# CruiseControlSystemWiringSchematic_11_28.net
KiCad netlist of a schematic drawn in EasyEDA
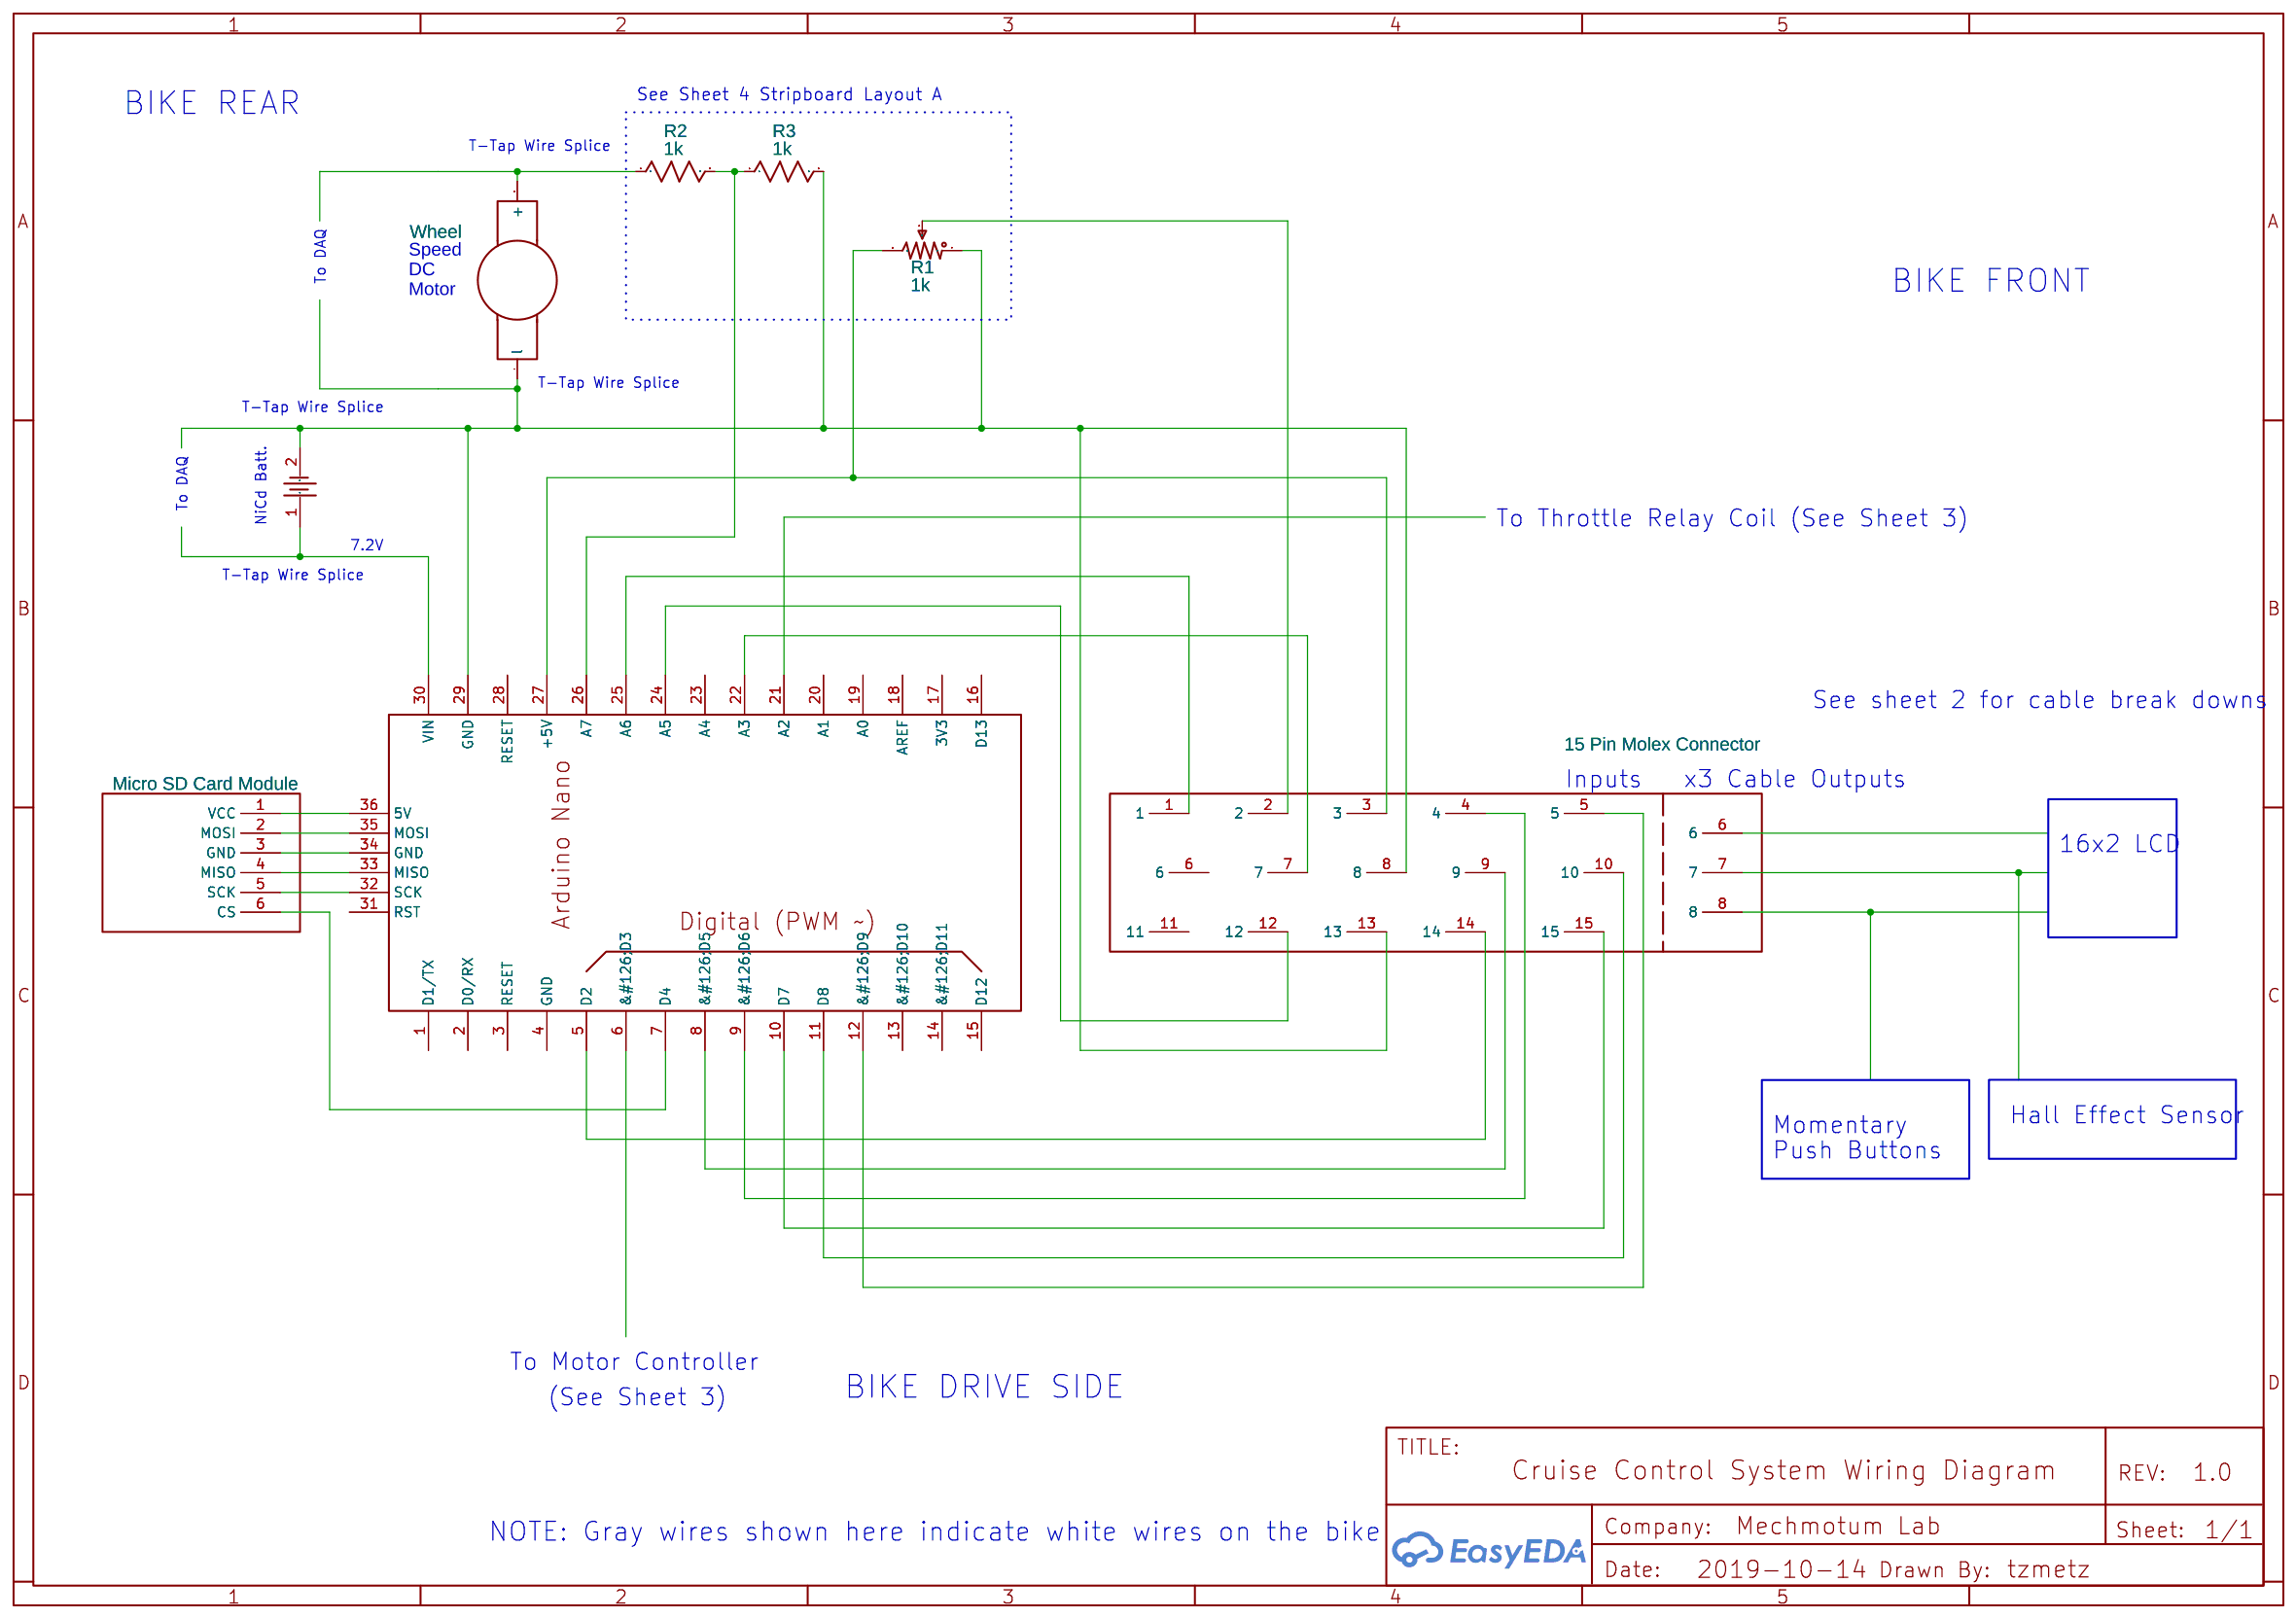
[diagram p0: Sheet_1]
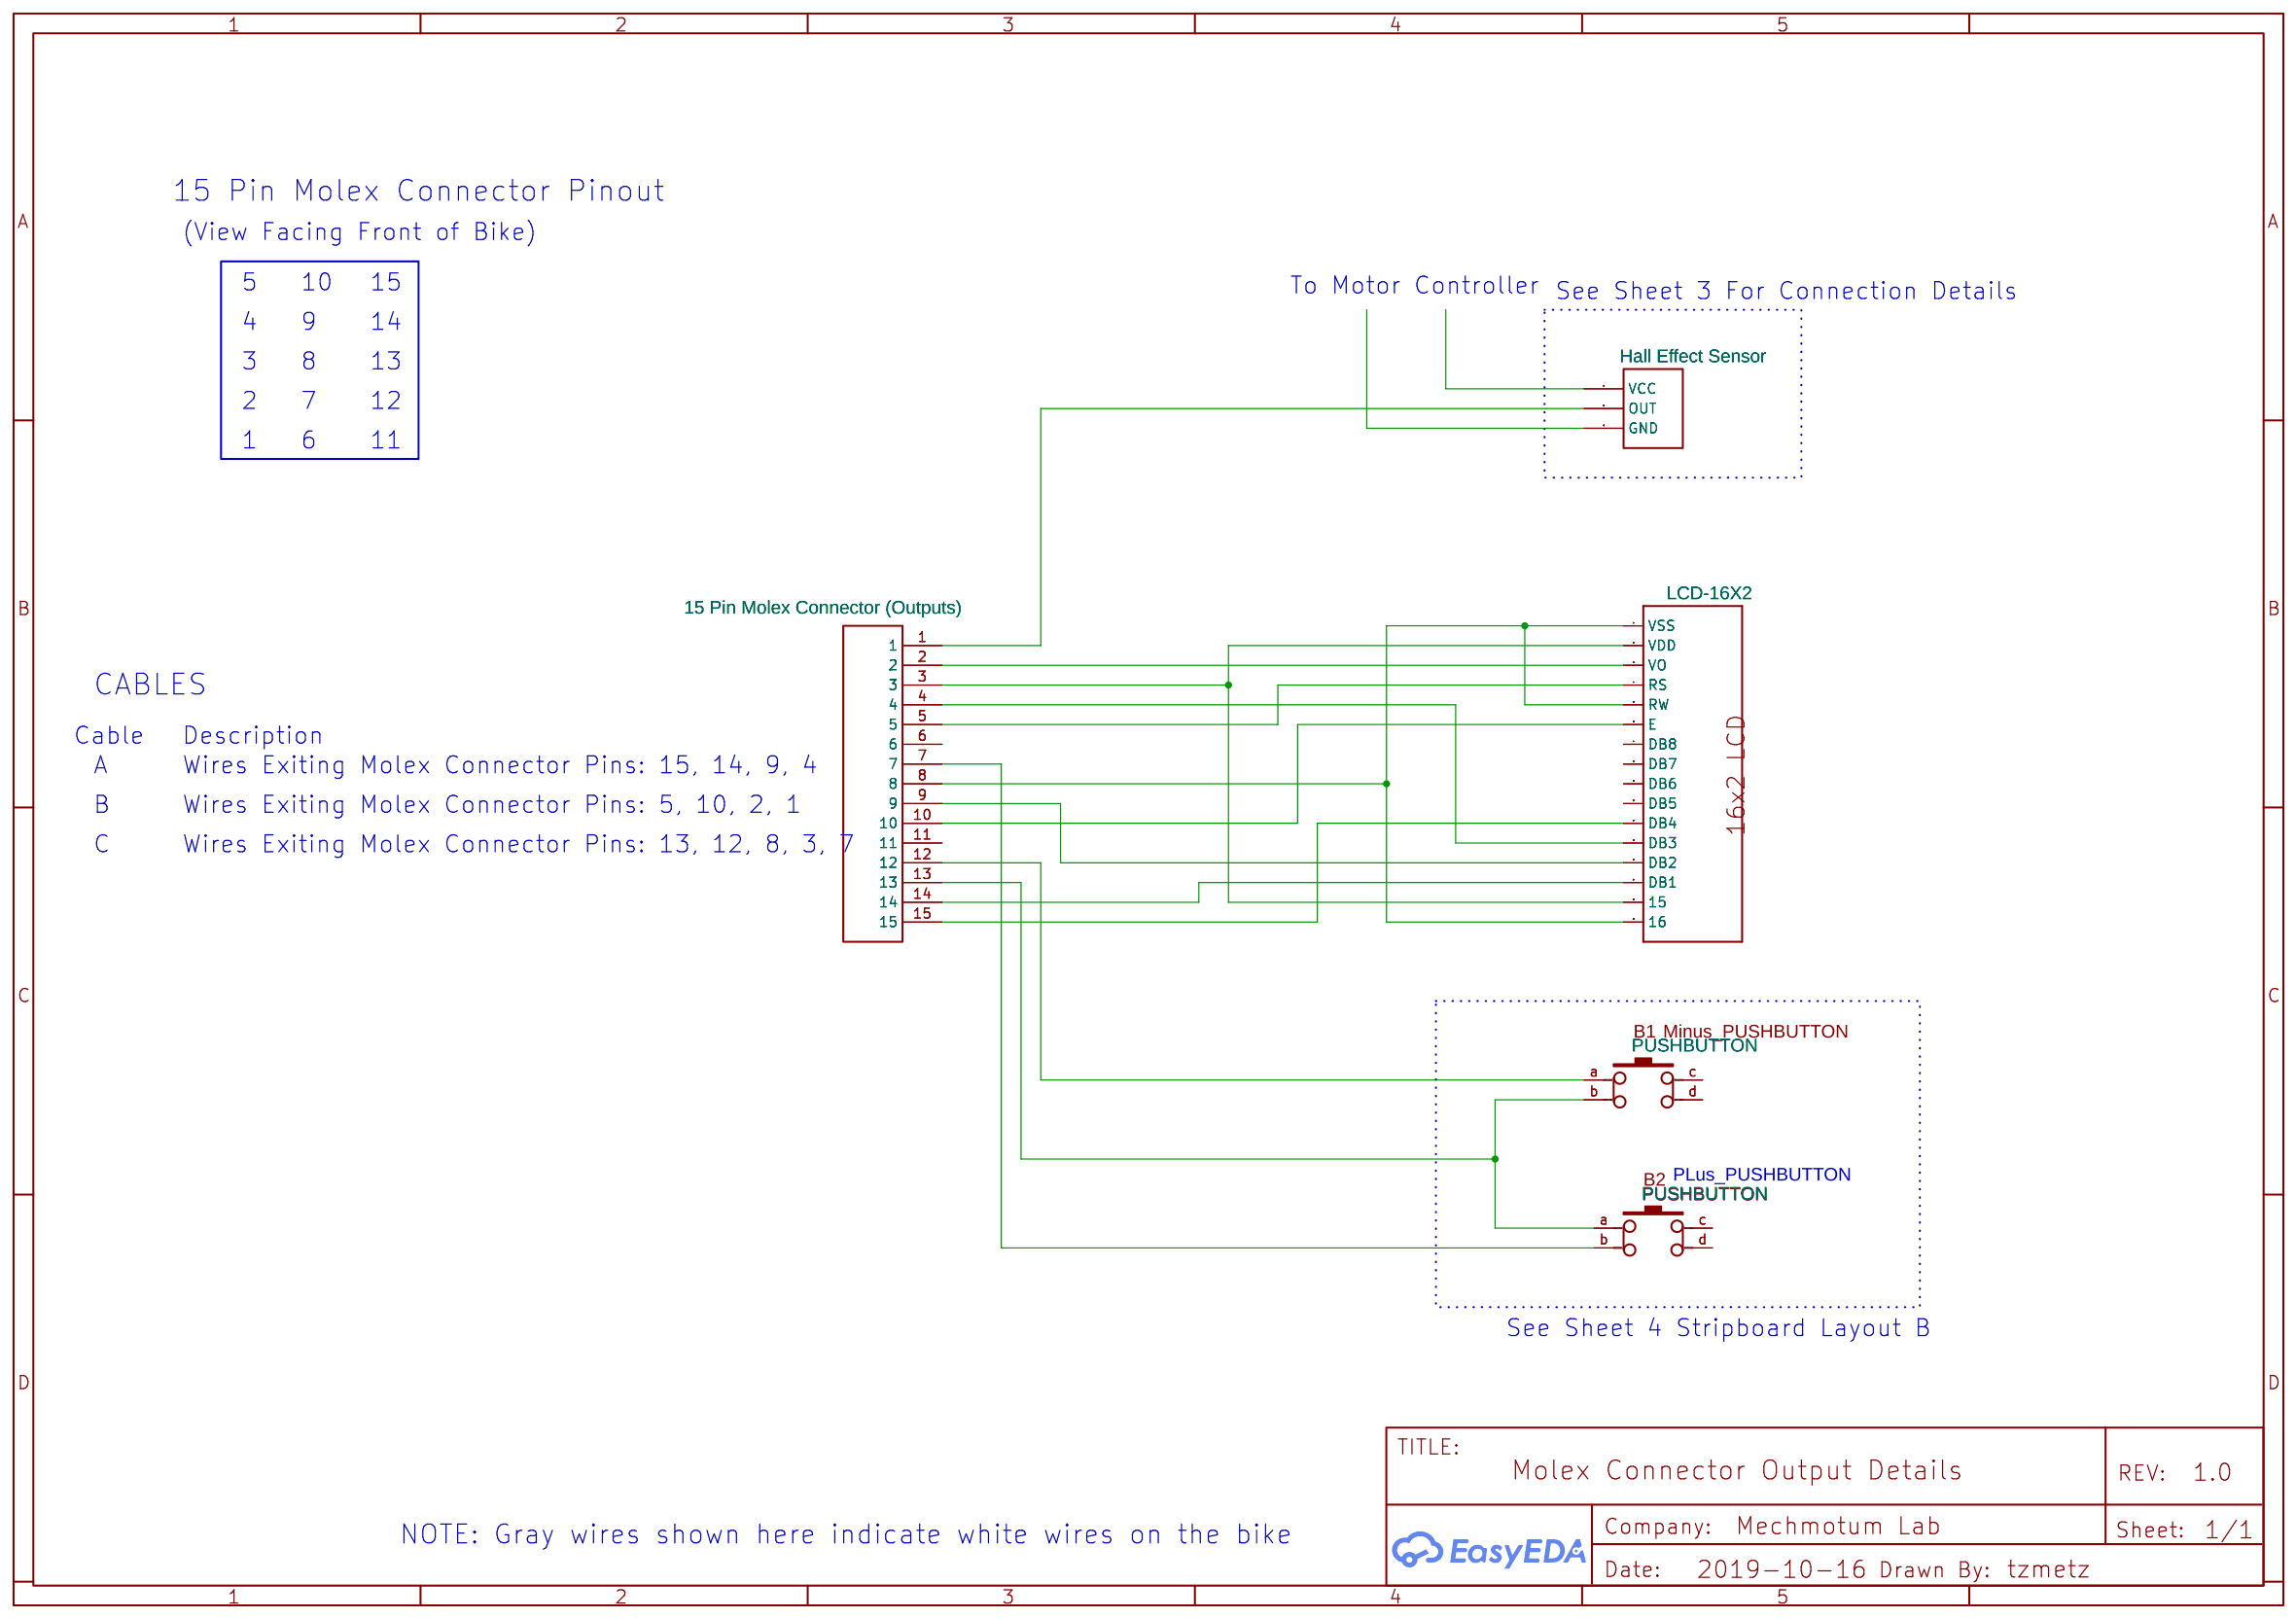
[diagram p1: Sheet_2]
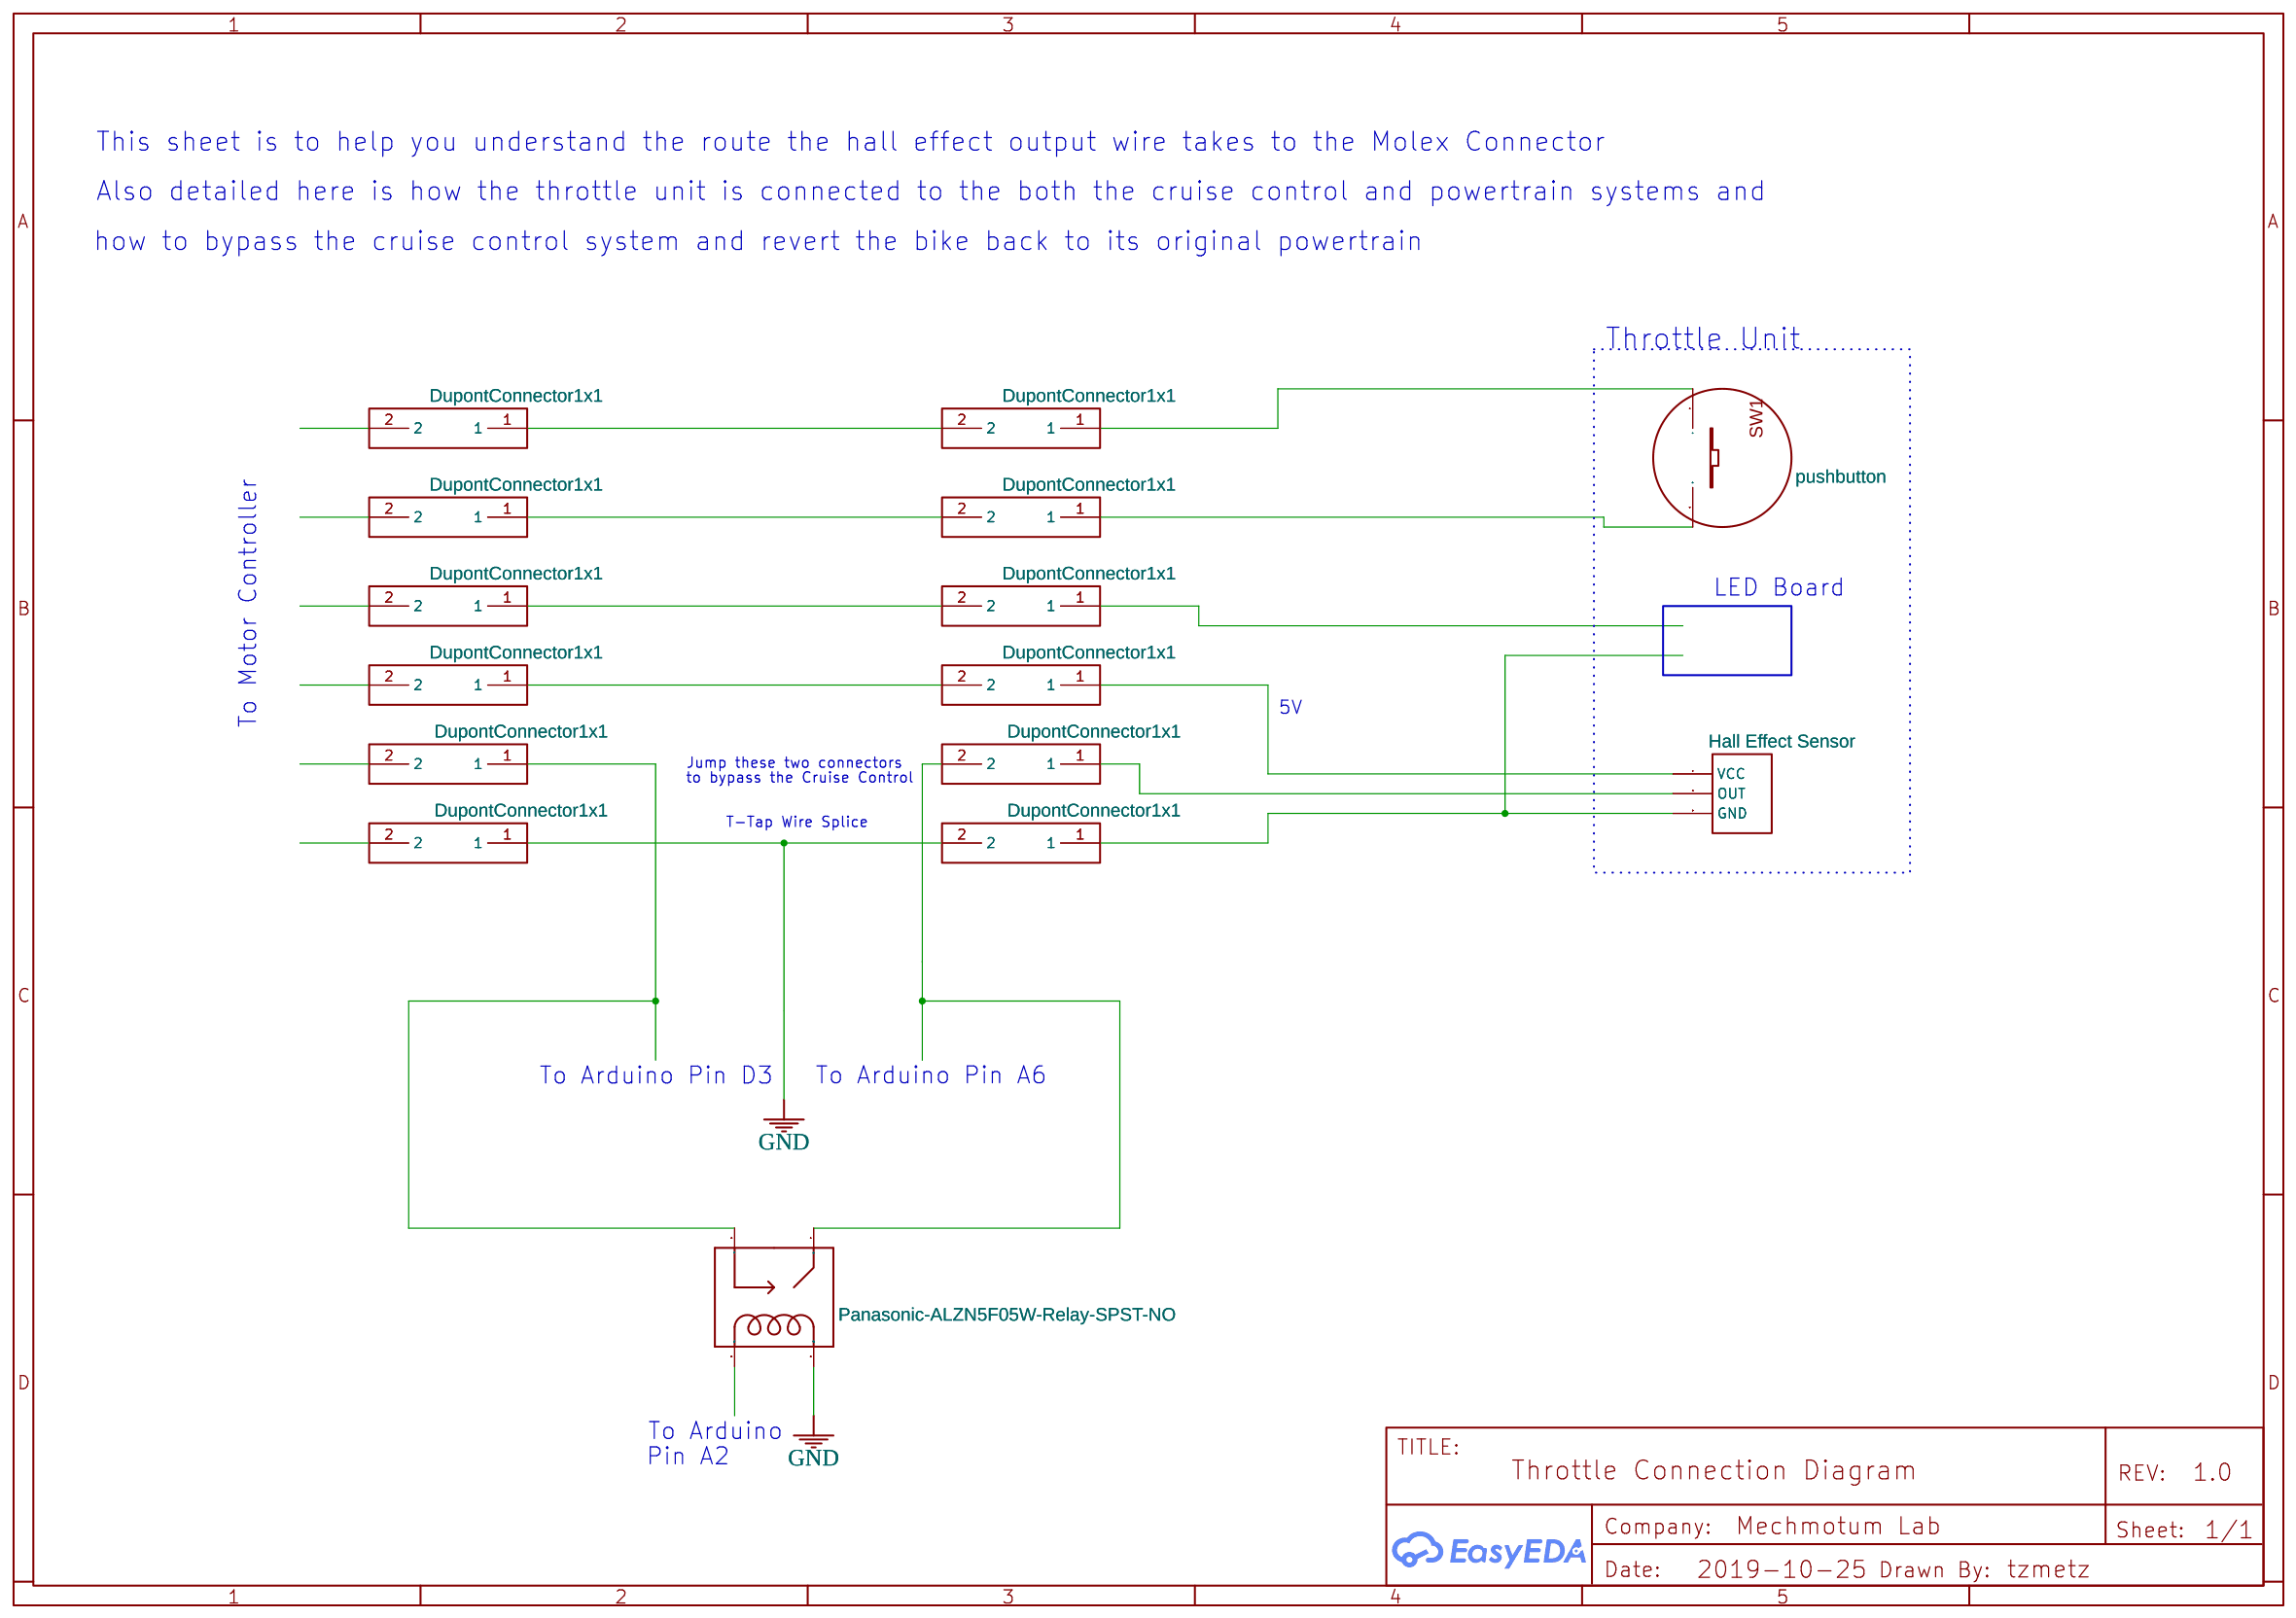
[diagram p2: Sheet_3]
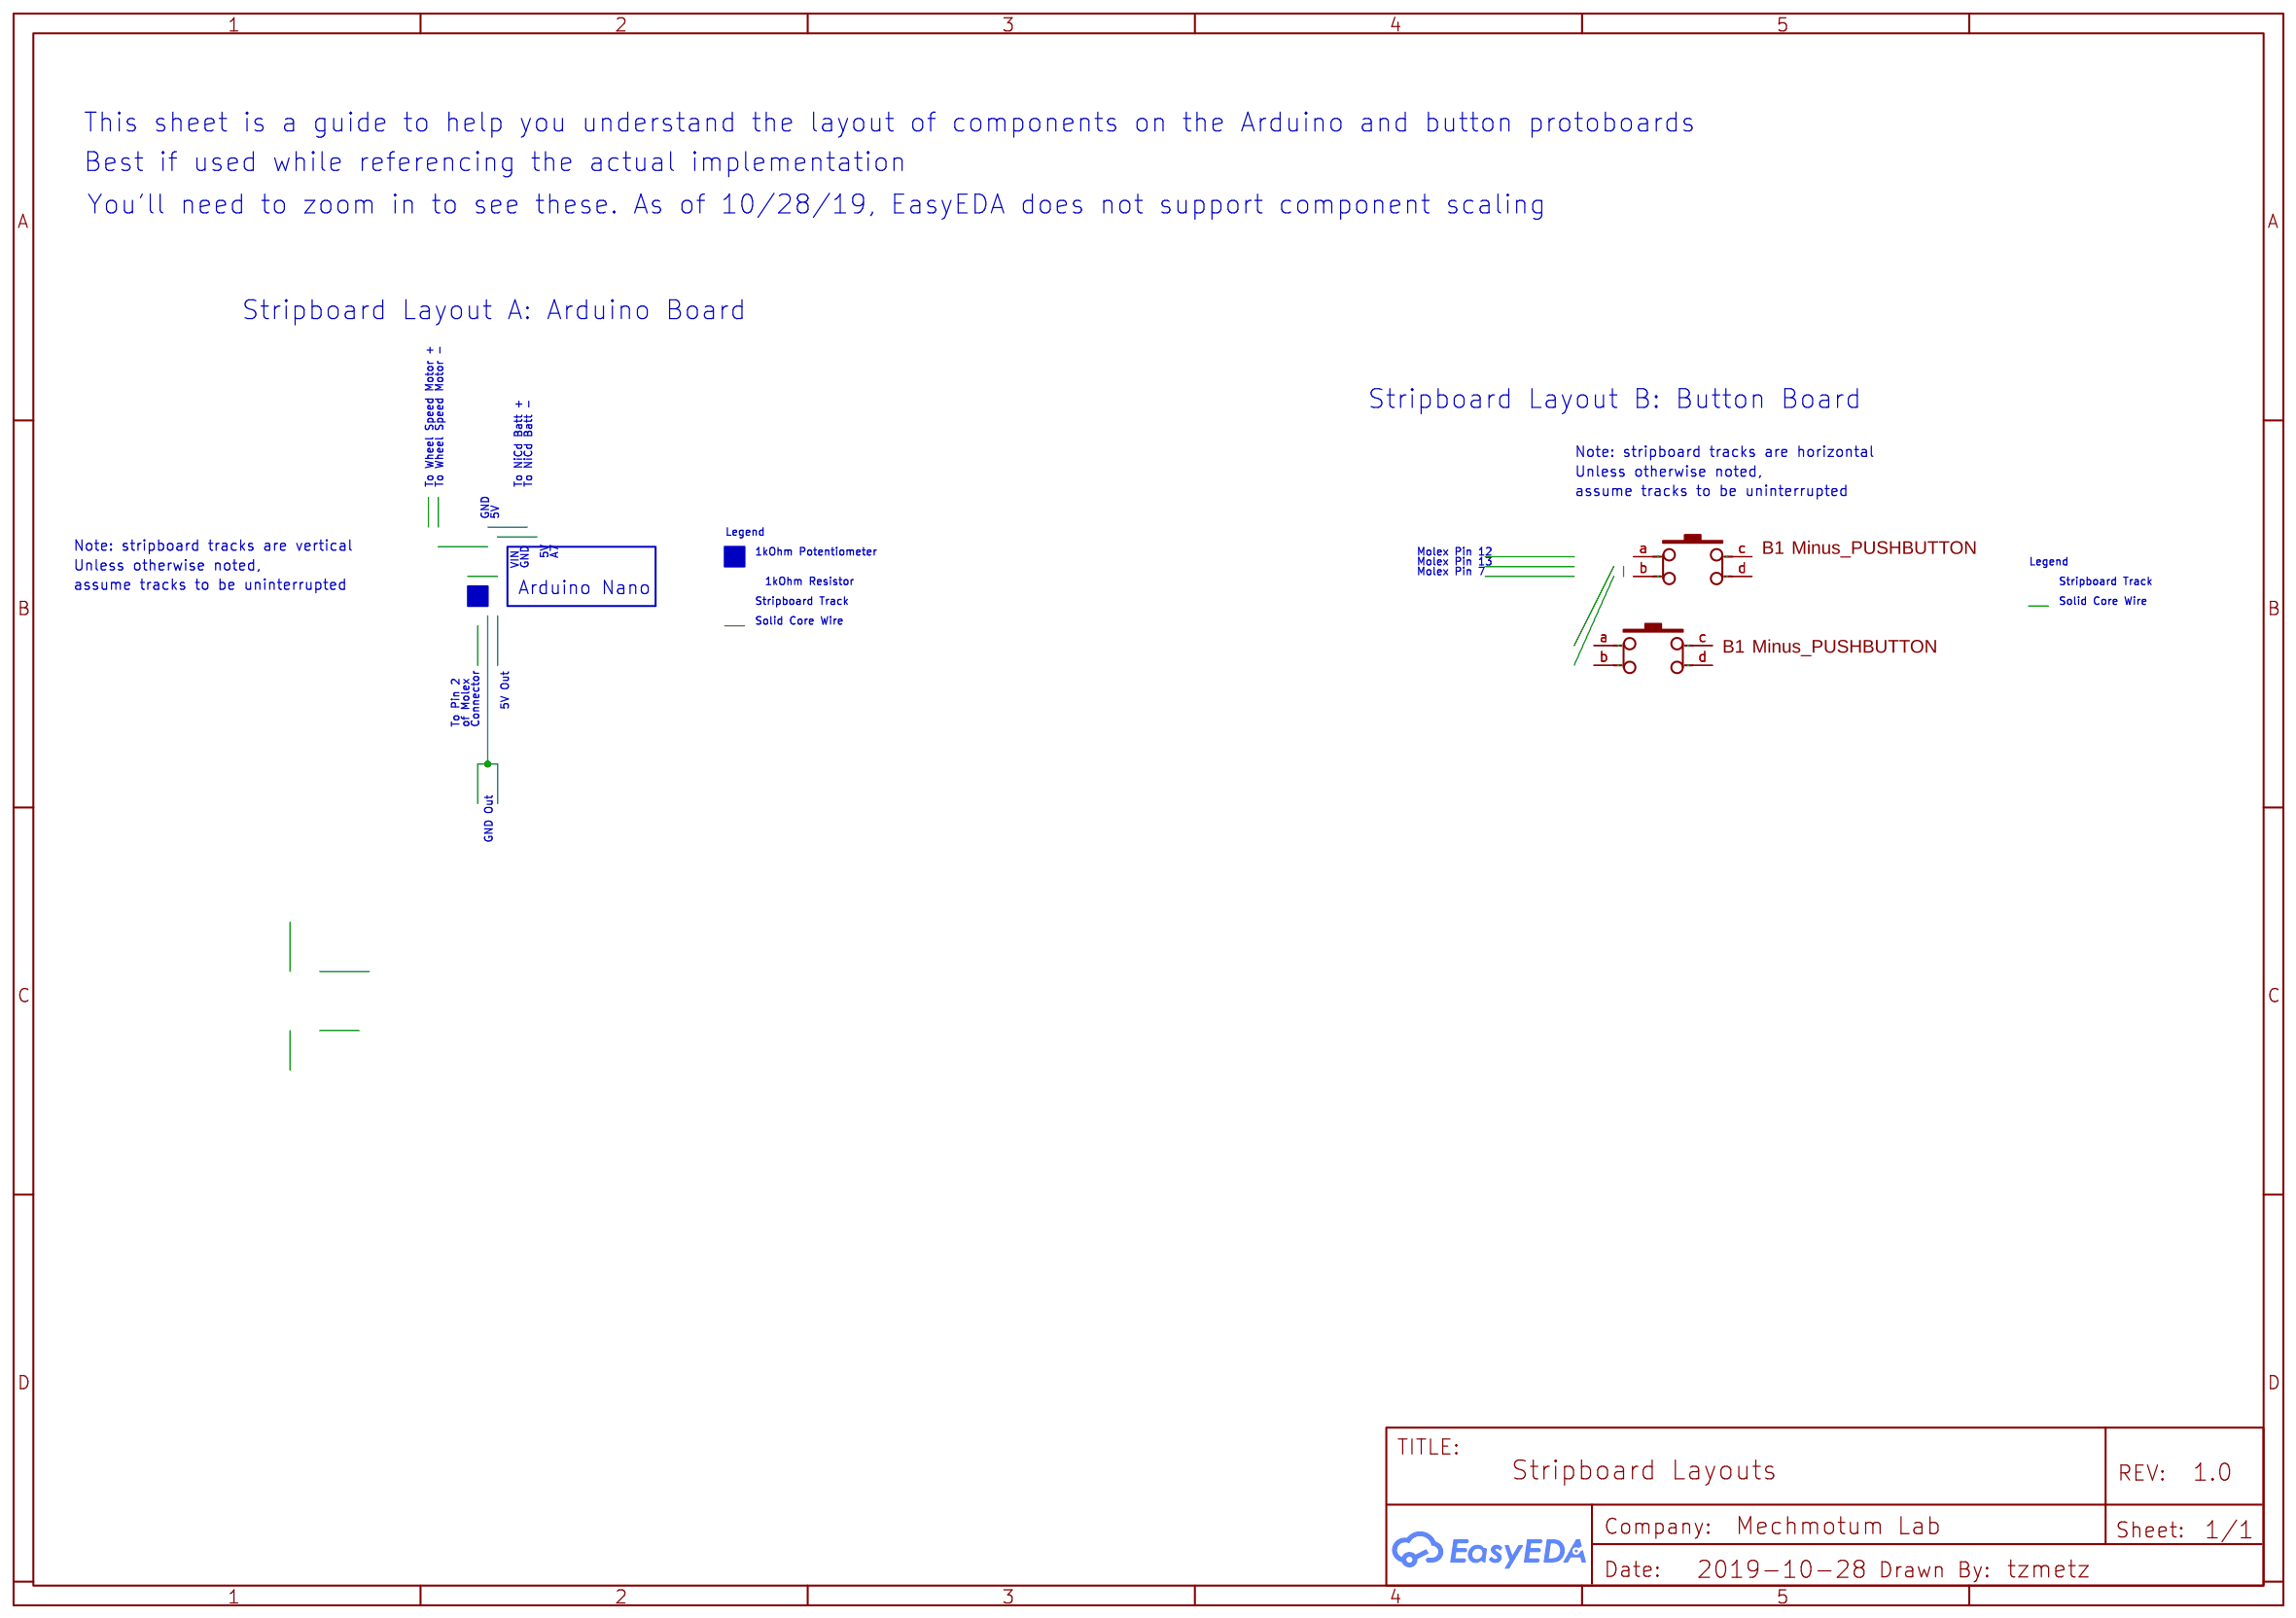
[diagram p3: Sheet_4]
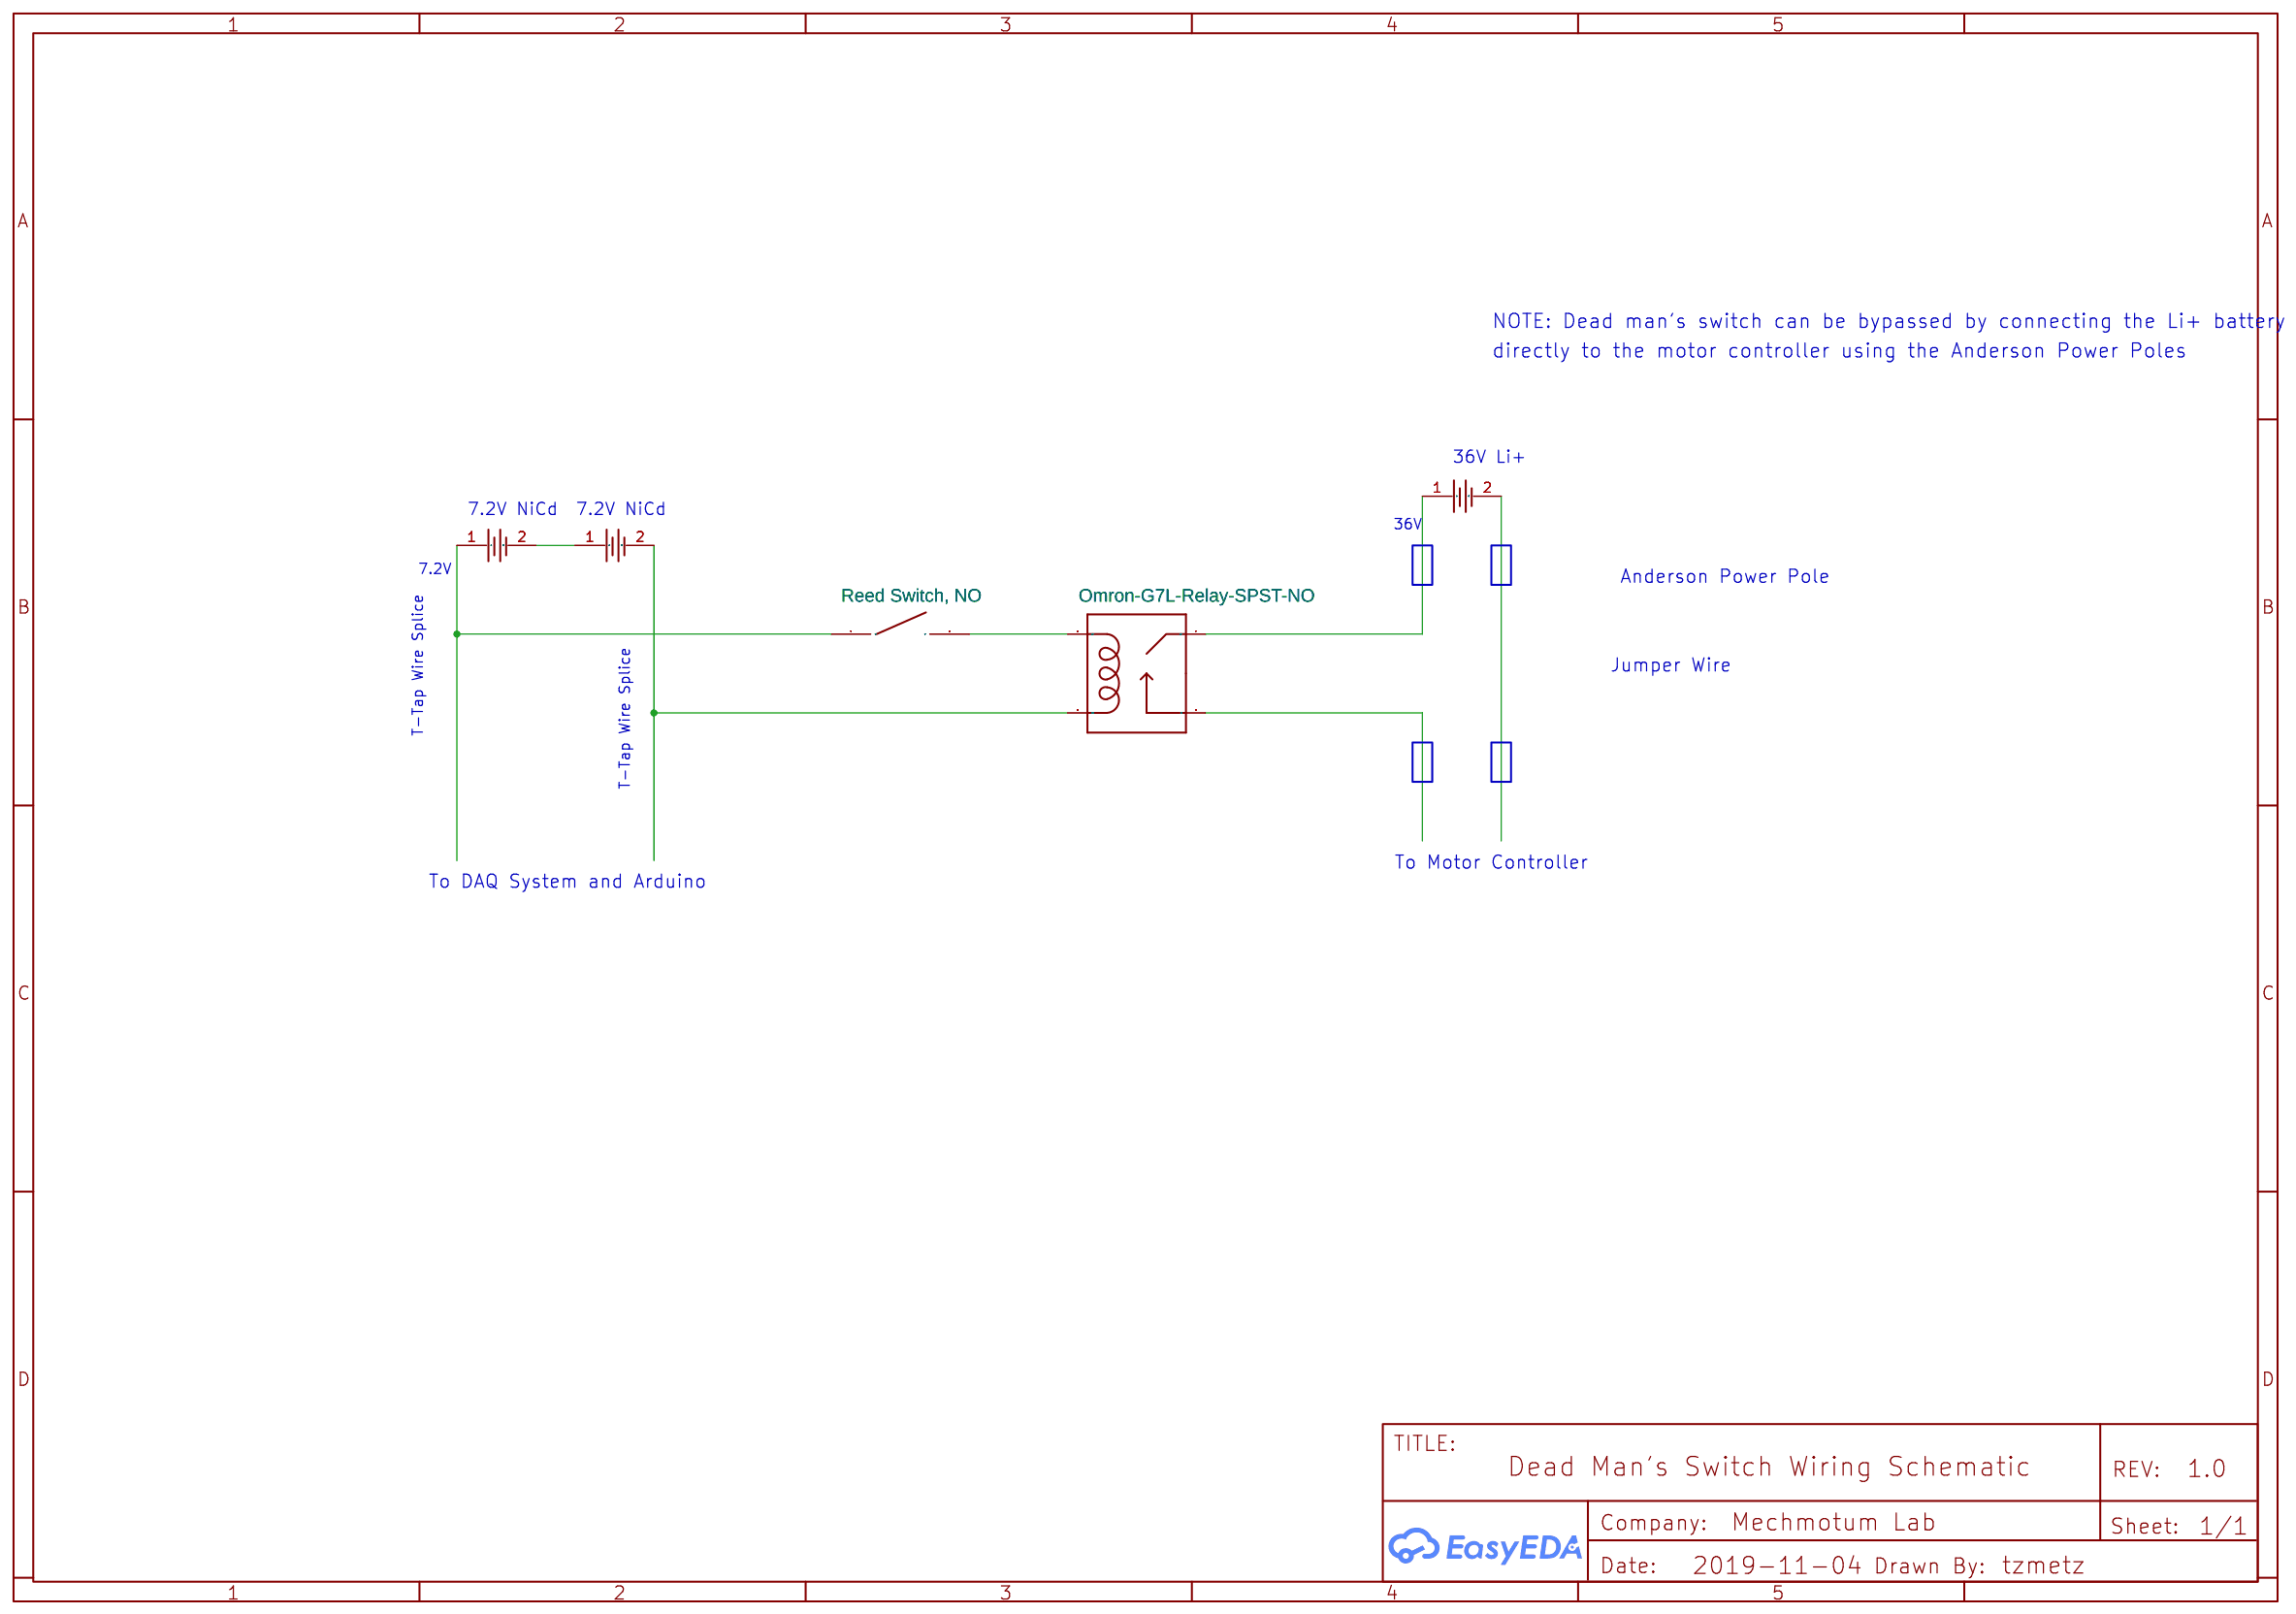
[diagram p4: Sheet_5]

(export (version "E")
  (design (tool "Eeschema 10.0.6"))
  (components
    (comp (ref "B1")
      (value "NiCd Battery 7.2V Line")
      (fields (field (name "BOM_Manufacturer Part") "BS-2-1") (field (name "BOM_Supplier Part") "C70376"))
      (libsource (lib "") (part "Unknown_145_240"))
    )
    (comp (ref "R1")
      (value "1k")
      (fields
        (field (name "BOM_Manufacturer Part") "3386P-1-101LF")
        (field (name "BOM_Supplier Part") "C125022")
      )
      (libsource (lib "") (part "3386P-1-101LF_US"))
    )
    (comp (ref "R2") (value "1k") (libsource (lib "") (part "Res_AXIAL-0.3(1/8W)_US")))
    (comp (ref "R3") (value "1k") (libsource (lib "") (part "Res_AXIAL-0.3(1/8W)_US")))
    (comp (ref "U2")
      (value "ARDUINO_NANO COPY")
      (fields (field (name "BOM_Manufacturer Part") "ARDUINO_NANO_LIVETHINGS"))
      (libsource (lib "") (part "Unknown_350_425"))
    )
    (comp (ref "U5") (value "Wheel") (libsource (lib "") (part "Unknown_255_135")))
    (comp (ref "U8") (value "Micro SD Card Module") (libsource (lib "") (part "Unknown_105_425")))
    (comp (ref "U10") (value "15 Pin Molex Connector") (libsource (lib "") (part "Unknown_635_435")))
    (comp (ref "U1") (value "PUSHBUTTON") (libsource (lib "") (part "Unknown_860_635")))
    (comp (ref "U6") (value "15 Pin Molex Connector (Outputs)") (libsource (lib "") (part "Unknown_450_310")))
    (comp (ref "U11") (value "LCD-16X2") (libsource (lib "") (part "Unknown_845_385")))
    (comp (ref "U12") (value "PUSHBUTTON") (libsource (lib "") (part "Unknown_855_560")))
    (comp (ref "U13") (value "Hall Effect Sensor") (libsource (lib "") (part "Unknown_795_180")))
    (comp (ref "RL2")
      (value "Panasonic-ALZN5F05W-Relay-SPST-NO")
      (libsource (lib "") (part "Unknown_385_645"))
    )
    (comp (ref "U3")
      (value "pushbutton")
      (fields (field (name "BOM_Manufacturer Part") "push button"))
      (libsource (lib "") (part "Unknown_875_220"))
    )
    (comp (ref "U4") (value "Hall Effect Sensor") (libsource (lib "") (part "Unknown_840_375")))
    (comp (ref "U7") (value "DupontConnector1x1") (libsource (lib "") (part "Unknown_510_380")))
    (comp (ref "U9") (value "DupontConnector1x1") (libsource (lib "") (part "Unknown_510_420")))
    (comp (ref "U14") (value "DupontConnector1x1") (libsource (lib "") (part "Unknown_510_300")))
    (comp (ref "U15") (value "DupontConnector1x1") (libsource (lib "") (part "Unknown_510_340")))
    (comp (ref "U16") (value "DupontConnector1x1") (libsource (lib "") (part "Unknown_510_255")))
    (comp (ref "U17") (value "DupontConnector1x1") (libsource (lib "") (part "Unknown_510_210")))
    (comp (ref "U18") (value "DupontConnector1x1") (libsource (lib "") (part "Unknown_220_210")))
    (comp (ref "U19") (value "DupontConnector1x1") (libsource (lib "") (part "Unknown_220_255")))
    (comp (ref "U20") (value "DupontConnector1x1") (libsource (lib "") (part "Unknown_220_340")))
    (comp (ref "U21") (value "DupontConnector1x1") (libsource (lib "") (part "Unknown_220_300")))
    (comp (ref "U22") (value "DupontConnector1x1") (libsource (lib "") (part "Unknown_220_420")))
    (comp (ref "U23") (value "DupontConnector1x1") (libsource (lib "") (part "Unknown_220_380")))
    (comp (ref "U24") (value "PUSHBUTTON") (libsource (lib "") (part "Unknown_880_295")))
    (comp (ref "U25") (value "PUSHBUTTON") (libsource (lib "") (part "Unknown_860_340")))
    (comp (ref "B2")
      (value "BS-2-1")
      (fields (field (name "BOM_Supplier Part") "C70376"))
      (libsource (lib "") (part "Unknown_245_270"))
    )
    (comp (ref "B3")
      (value "BS-2-1")
      (fields (field (name "BOM_Supplier Part") "C70376"))
      (libsource (lib "") (part "Unknown_305_270"))
    )
    (comp (ref "B4")
      (value "BS-2-1")
      (fields (field (name "BOM_Supplier Part") "C70376"))
      (libsource (lib "") (part "Unknown_735_245"))
    )
    (comp (ref "RL1") (value "Omron-G7L-Relay-SPST-NO") (libsource (lib "") (part "Unknown_575_335")))
    (comp (ref "SW1")
      (value "Reed Switch, NO")
      (fields (field (name "BOM_Manufacturer Part") "EVQ22705R") (field (name "BOM_Supplier Part") "C79156"))
      (libsource (lib "") (part "Unknown_450_315"))
    )
  )
  (nets
    (net (code "1") (name "GND") (class "Default")
      (node (ref "RL2") (pin "2") (pinfunction "COIL2_2") (pintype "unspecified"))
      (node (ref "U22") (pin "1") (pinfunction "1_1") (pintype "unspecified"))
      (node (ref "U9") (pin "2") (pinfunction "2_2") (pintype "unspecified"))
    )
    (net (code "2") (name "Net-(B2-Pad1)") (class "Default")
      (node (ref "B2") (pin "1") (pinfunction "1_1") (pintype "input"))
      (node (ref "SW1") (pin "1") (pinfunction "1_1") (pintype "input"))
    )
    (net (code "3") (name "Net-(B2-Pad2)") (class "Default")
      (node (ref "B2") (pin "2") (pinfunction "2_2") (pintype "input"))
      (node (ref "B3") (pin "1") (pinfunction "1_1") (pintype "input"))
    )
    (net (code "4") (name "Net-(R1-Pad2)") (class "Default")
      (node (ref "R1") (pin "2") (pinfunction "2_2") (pintype "unspecified"))
      (node (ref "U10") (pin "2") (pinfunction "2_2") (pintype "unspecified"))
    )
    (net (code "5") (name "Net-(RL1-COIL1)") (class "Default")
      (node (ref "B3") (pin "2") (pinfunction "2_2") (pintype "input"))
      (node (ref "RL1") (pin "5") (pinfunction "COIL1_5") (pintype "unspecified"))
    )
    (net (code "6") (name "Net-(RL1-COIL2)") (class "Default")
      (node (ref "RL1") (pin "2") (pinfunction "COIL2_2") (pintype "unspecified"))
      (node (ref "SW1") (pin "2") (pinfunction "2_2") (pintype "input"))
    )
    (net (code "7") (name "Net-(RL1-MAIN)") (class "Default")
      (node (ref "B4") (pin "1") (pinfunction "1_1") (pintype "input"))
      (node (ref "RL1") (pin "1") (pinfunction "MAIN_1") (pintype "unspecified"))
    )
    (net (code "8") (name "Net-(RL2-MAIN)") (class "Default")
      (node (ref "RL2") (pin "1") (pinfunction "MAIN_1") (pintype "unspecified"))
      (node (ref "U7") (pin "2") (pinfunction "2_2") (pintype "unspecified"))
    )
    (net (code "9") (name "Net-(RL2-NO)") (class "Default")
      (node (ref "RL2") (pin "3") (pinfunction "NO_3") (pintype "unspecified"))
      (node (ref "U23") (pin "1") (pinfunction "1_1") (pintype "unspecified"))
    )
    (net (code "10") (name "Net-(U1-1-Pada)") (class "Default")
      (node (ref "U1") (pin "a") (pinfunction "1_a") (pintype "input"))
      (node (ref "U12") (pin "b") (pinfunction "1_b") (pintype "input"))
      (node (ref "U6") (pin "13") (pinfunction "13_13") (pintype "unspecified"))
    )
    (net (code "11") (name "Net-(U1-1-Padb)") (class "Default")
      (node (ref "U1") (pin "b") (pinfunction "1_b") (pintype "input"))
      (node (ref "U6") (pin "7") (pinfunction "7_7") (pintype "unspecified"))
    )
    (net (code "12") (name "Net-(U2-&#126;D5)") (class "Default")
      (node (ref "U10") (pin "9") (pinfunction "9_9") (pintype "unspecified"))
      (node (ref "U2") (pin "8") (pinfunction "&#126;D5_8") (pintype "unspecified"))
    )
    (net (code "13") (name "Net-(U2-&#126;D6)") (class "Default")
      (node (ref "U10") (pin "4") (pinfunction "4_4") (pintype "unspecified"))
      (node (ref "U2") (pin "9") (pinfunction "&#126;D6_9") (pintype "unspecified"))
    )
    (net (code "14") (name "Net-(U2-&#126;D9)") (class "Default")
      (node (ref "U10") (pin "5") (pinfunction "5_5") (pintype "unspecified"))
      (node (ref "U2") (pin "12") (pinfunction "&#126;D9_12") (pintype "unspecified"))
    )
    (net (code "15") (name "Net-(U2-+5V)") (class "Default")
      (node (ref "R1") (pin "3") (pinfunction "3_3") (pintype "unspecified"))
      (node (ref "U10") (pin "3") (pinfunction "3_3") (pintype "unspecified"))
      (node (ref "U2") (pin "27") (pinfunction "+5V_27") (pintype "unspecified"))
    )
    (net (code "16") (name "Net-(U2-5V)") (class "Default")
      (node (ref "U2") (pin "36") (pinfunction "5V_36") (pintype "unspecified"))
      (node (ref "U8") (pin "1") (pinfunction "VCC_1") (pintype "unspecified"))
    )
    (net (code "17") (name "Net-(U2-A3)") (class "Default")
      (node (ref "U10") (pin "7") (pinfunction "7_7") (pintype "unspecified"))
      (node (ref "U2") (pin "22") (pinfunction "A3_22") (pintype "unspecified"))
    )
    (net (code "18") (name "Net-(U2-A5)") (class "Default")
      (node (ref "U10") (pin "12") (pinfunction "12_12") (pintype "unspecified"))
      (node (ref "U2") (pin "24") (pinfunction "A5_24") (pintype "unspecified"))
    )
    (net (code "19") (name "Net-(U2-A6)") (class "Default")
      (node (ref "U10") (pin "1") (pinfunction "1_1") (pintype "unspecified"))
      (node (ref "U2") (pin "25") (pinfunction "A6_25") (pintype "unspecified"))
    )
    (net (code "20") (name "Net-(U2-A7)") (class "Default")
      (node (ref "R2") (pin "2") (pinfunction "2_2") (pintype "unspecified"))
      (node (ref "R3") (pin "1") (pinfunction "1_1") (pintype "unspecified"))
      (node (ref "U2") (pin "26") (pinfunction "A7_26") (pintype "unspecified"))
    )
    (net (code "21") (name "Net-(U2-D2)") (class "Default")
      (node (ref "U10") (pin "14") (pinfunction "14_14") (pintype "unspecified"))
      (node (ref "U2") (pin "5") (pinfunction "D2_5") (pintype "unspecified"))
    )
    (net (code "22") (name "Net-(U2-D4)") (class "Default")
      (node (ref "U2") (pin "7") (pinfunction "D4_7") (pintype "unspecified"))
      (node (ref "U8") (pin "6") (pinfunction "CS_6") (pintype "unspecified"))
    )
    (net (code "23") (name "Net-(U2-D7)") (class "Default")
      (node (ref "U10") (pin "15") (pinfunction "15_15") (pintype "unspecified"))
      (node (ref "U2") (pin "10") (pinfunction "D7_10") (pintype "unspecified"))
    )
    (net (code "24") (name "Net-(U2-D8)") (class "Default")
      (node (ref "U10") (pin "10") (pinfunction "10_10") (pintype "unspecified"))
      (node (ref "U2") (pin "11") (pinfunction "D8_11") (pintype "unspecified"))
    )
    (net (code "25") (name "Net-(U2-MISO)") (class "Default")
      (node (ref "U2") (pin "33") (pinfunction "MISO_33") (pintype "unspecified"))
      (node (ref "U8") (pin "4") (pinfunction "MISO_4") (pintype "unspecified"))
    )
    (net (code "26") (name "Net-(U2-MOSI)") (class "Default")
      (node (ref "U2") (pin "35") (pinfunction "MOSI_35") (pintype "unspecified"))
      (node (ref "U8") (pin "2") (pinfunction "MOSI_2") (pintype "unspecified"))
    )
    (net (code "27") (name "Net-(U2-SCK)") (class "Default")
      (node (ref "U2") (pin "32") (pinfunction "SCK_32") (pintype "unspecified"))
      (node (ref "U8") (pin "5") (pinfunction "SCK_5") (pintype "unspecified"))
    )
    (net (code "28") (name "Net-(U2-VIN)") (class "Default")
      (node (ref "B1") (pin "1") (pinfunction "1_1") (pintype "input"))
      (node (ref "U2") (pin "30") (pinfunction "VIN_30") (pintype "unspecified"))
    )
    (net (code "29") (name "Net-(U4-GND)") (class "Default")
      (node (ref "U4") (pin "3") (pinfunction "GND_3") (pintype "unspecified"))
      (node (ref "U9") (pin "1") (pinfunction "1_1") (pintype "unspecified"))
    )
    (net (code "30") (name "Net-(U4-OUT)") (class "Default")
      (node (ref "U4") (pin "2") (pinfunction "OUT_2") (pintype "unspecified"))
      (node (ref "U7") (pin "1") (pinfunction "1_1") (pintype "unspecified"))
    )
    (net (code "31") (name "Net-(U4-VCC)") (class "Default")
      (node (ref "U15") (pin "1") (pinfunction "1_1") (pintype "unspecified"))
      (node (ref "U4") (pin "1") (pinfunction "VCC_1") (pintype "unspecified"))
    )
    (net (code "32") (name "Net-(U5-+)") (class "Default")
      (node (ref "R2") (pin "1") (pinfunction "1_1") (pintype "unspecified"))
      (node (ref "U5") (pin "1") (pinfunction "+_1") (pintype "unspecified"))
    )
    (net (code "33") (name "Net-(U5-l)") (class "Default")
      (node (ref "B1") (pin "2") (pinfunction "2_2") (pintype "input"))
      (node (ref "R1") (pin "1") (pinfunction "1_1") (pintype "unspecified"))
      (node (ref "R3") (pin "2") (pinfunction "2_2") (pintype "unspecified"))
      (node (ref "U10") (pin "13") (pinfunction "13_13") (pintype "unspecified"))
      (node (ref "U10") (pin "8") (pinfunction "8_8") (pintype "unspecified"))
      (node (ref "U2") (pin "29") (pinfunction "GND_29") (pintype "unspecified"))
      (node (ref "U5") (pin "-") (pinfunction "l_-") (pintype "unspecified"))
    )
    (net (code "34") (name "Net-(U8-GND)") (class "Default")
      (node (ref "U2") (pin "34") (pinfunction "GND_34") (pintype "unspecified"))
      (node (ref "U8") (pin "3") (pinfunction "GND_3") (pintype "unspecified"))
    )
    (net (code "35") (name "Net-(U11-DB1)") (class "Default")
      (node (ref "U11") (pin "14") (pinfunction "DB1_14") (pintype "unspecified"))
      (node (ref "U6") (pin "14") (pinfunction "14_14") (pintype "unspecified"))
    )
    (net (code "36") (name "Net-(U11-DB2)") (class "Default")
      (node (ref "U11") (pin "13") (pinfunction "DB2_13") (pintype "unspecified"))
      (node (ref "U6") (pin "9") (pinfunction "9_9") (pintype "unspecified"))
    )
    (net (code "37") (name "Net-(U11-DB3)") (class "Default")
      (node (ref "U11") (pin "12") (pinfunction "DB3_12") (pintype "unspecified"))
      (node (ref "U6") (pin "4") (pinfunction "4_4") (pintype "unspecified"))
    )
    (net (code "38") (name "Net-(U11-DB4)") (class "Default")
      (node (ref "U11") (pin "11") (pinfunction "DB4_11") (pintype "unspecified"))
      (node (ref "U6") (pin "15") (pinfunction "15_15") (pintype "unspecified"))
    )
    (net (code "39") (name "Net-(U11-E)") (class "Default")
      (node (ref "U11") (pin "6") (pinfunction "E_6") (pintype "input"))
      (node (ref "U6") (pin "10") (pinfunction "10_10") (pintype "unspecified"))
    )
    (net (code "40") (name "Net-(U11-RS)") (class "Default")
      (node (ref "U11") (pin "4") (pinfunction "RS_4") (pintype "input"))
      (node (ref "U6") (pin "5") (pinfunction "5_5") (pintype "unspecified"))
    )
    (net (code "41") (name "Net-(U11-RW)") (class "Default")
      (node (ref "U11") (pin "1") (pinfunction "VSS_1") (pintype "passive"))
      (node (ref "U11") (pin "16") (pinfunction "16_16") (pintype "passive"))
      (node (ref "U11") (pin "5") (pinfunction "RW_5") (pintype "input"))
      (node (ref "U6") (pin "8") (pinfunction "8_8") (pintype "unspecified"))
    )
    (net (code "42") (name "Net-(U11-VDD)") (class "Default")
      (node (ref "U11") (pin "15") (pinfunction "15_15") (pintype "passive"))
      (node (ref "U11") (pin "2") (pinfunction "VDD_2") (pintype "passive"))
      (node (ref "U6") (pin "3") (pinfunction "3_3") (pintype "unspecified"))
    )
    (net (code "43") (name "Net-(U11-VO)") (class "Default")
      (node (ref "U11") (pin "3") (pinfunction "VO_3") (pintype "unspecified"))
      (node (ref "U6") (pin "2") (pinfunction "2_2") (pintype "unspecified"))
    )
    (net (code "44") (name "Net-(U12-1-Pada)") (class "Default")
      (node (ref "U12") (pin "a") (pinfunction "1_a") (pintype "input"))
      (node (ref "U6") (pin "12") (pinfunction "12_12") (pintype "unspecified"))
    )
    (net (code "45") (name "Net-(U13-OUT)") (class "Default")
      (node (ref "U13") (pin "2") (pinfunction "OUT_2") (pintype "unspecified"))
      (node (ref "U6") (pin "1") (pinfunction "1_1") (pintype "unspecified"))
    )
    (net (code "46") (name "Net-(U14-Pad2)") (class "Default")
      (node (ref "U14") (pin "2") (pinfunction "2_2") (pintype "unspecified"))
      (node (ref "U21") (pin "1") (pinfunction "1_1") (pintype "unspecified"))
    )
    (net (code "47") (name "Net-(U15-Pad2)") (class "Default")
      (node (ref "U15") (pin "2") (pinfunction "2_2") (pintype "unspecified"))
      (node (ref "U20") (pin "1") (pinfunction "1_1") (pintype "unspecified"))
    )
    (net (code "48") (name "Net-(U16-Pad1)") (class "Default")
      (node (ref "U16") (pin "1") (pinfunction "1_1") (pintype "unspecified"))
      (node (ref "U3") (pin "2") (pinfunction "2_2") (pintype "input"))
    )
    (net (code "49") (name "Net-(U16-Pad2)") (class "Default")
      (node (ref "U16") (pin "2") (pinfunction "2_2") (pintype "unspecified"))
      (node (ref "U19") (pin "1") (pinfunction "1_1") (pintype "unspecified"))
    )
    (net (code "50") (name "Net-(U17-Pad1)") (class "Default")
      (node (ref "U17") (pin "1") (pinfunction "1_1") (pintype "unspecified"))
      (node (ref "U3") (pin "1") (pinfunction "1_1") (pintype "input"))
    )
    (net (code "51") (name "Net-(U17-Pad2)") (class "Default")
      (node (ref "U17") (pin "2") (pinfunction "2_2") (pintype "unspecified"))
      (node (ref "U18") (pin "1") (pinfunction "1_1") (pintype "unspecified"))
    )
    (net (code "52") (name "unconnected-(B4-Pad2)") (class "Default")
      (node (ref "B4") (pin "2") (pinfunction "2_2") (pintype "input"))
    )
    (net (code "53") (name "unconnected-(RL1-NO-Pad3)") (class "Default")
      (node (ref "RL1") (pin "3") (pinfunction "NO_3") (pintype "unspecified"))
    )
    (net (code "54") (name "unconnected-(RL2-COIL1-Pad5)") (class "Default")
      (node (ref "RL2") (pin "5") (pinfunction "COIL1_5") (pintype "unspecified"))
    )
    (net (code "55") (name "unconnected-(U1-2-Padd)") (class "Default")
      (node (ref "U1") (pin "d") (pinfunction "2_d") (pintype "input"))
    )
    (net (code "56") (name "unconnected-(U1-3-Padc)") (class "Default")
      (node (ref "U1") (pin "c") (pinfunction "3_c") (pintype "input"))
    )
    (net (code "57") (name "unconnected-(U2-&#126;D3-Pad6)") (class "Default")
      (node (ref "U2") (pin "6") (pinfunction "&#126;D3_6") (pintype "unspecified"))
    )
    (net (code "58") (name "unconnected-(U2-&#126;D10-Pad13)") (class "Default")
      (node (ref "U2") (pin "13") (pinfunction "&#126;D10_13") (pintype "unspecified"))
    )
    (net (code "59") (name "unconnected-(U2-&#126;D11-Pad14)") (class "Default")
      (node (ref "U2") (pin "14") (pinfunction "&#126;D11_14") (pintype "unspecified"))
    )
    (net (code "60") (name "unconnected-(U2-3V3-Pad17)") (class "Default")
      (node (ref "U2") (pin "17") (pinfunction "3V3_17") (pintype "unspecified"))
    )
    (net (code "61") (name "unconnected-(U2-A0-Pad19)") (class "Default")
      (node (ref "U2") (pin "19") (pinfunction "A0_19") (pintype "unspecified"))
    )
    (net (code "62") (name "unconnected-(U2-A1-Pad20)") (class "Default")
      (node (ref "U2") (pin "20") (pinfunction "A1_20") (pintype "unspecified"))
    )
    (net (code "63") (name "unconnected-(U2-A2-Pad21)") (class "Default")
      (node (ref "U2") (pin "21") (pinfunction "A2_21") (pintype "unspecified"))
    )
    (net (code "64") (name "unconnected-(U2-A4-Pad23)") (class "Default")
      (node (ref "U2") (pin "23") (pinfunction "A4_23") (pintype "unspecified"))
    )
    (net (code "65") (name "unconnected-(U2-AREF-Pad18)") (class "Default")
      (node (ref "U2") (pin "18") (pinfunction "AREF_18") (pintype "unspecified"))
    )
    (net (code "66") (name "unconnected-(U2-D0{slash}RX-Pad2)") (class "Default")
      (node (ref "U2") (pin "2") (pinfunction "D0/RX_2") (pintype "unspecified"))
    )
    (net (code "67") (name "unconnected-(U2-D1{slash}TX-Pad1)") (class "Default")
      (node (ref "U2") (pin "1") (pinfunction "D1/TX_1") (pintype "unspecified"))
    )
    (net (code "68") (name "unconnected-(U2-D12-Pad15)") (class "Default")
      (node (ref "U2") (pin "15") (pinfunction "D12_15") (pintype "unspecified"))
    )
    (net (code "69") (name "unconnected-(U2-D13-Pad16)") (class "Default")
      (node (ref "U2") (pin "16") (pinfunction "D13_16") (pintype "unspecified"))
    )
    (net (code "70") (name "unconnected-(U2-GND-Pad4)") (class "Default")
      (node (ref "U2") (pin "4") (pinfunction "GND_4") (pintype "unspecified"))
    )
    (net (code "71") (name "unconnected-(U2-RESET-Pad3)") (class "Default")
      (node (ref "U2") (pin "3") (pinfunction "RESET_3") (pintype "unspecified"))
    )
    (net (code "72") (name "unconnected-(U2-RESET-Pad28)") (class "Default")
      (node (ref "U2") (pin "28") (pinfunction "RESET_28") (pintype "unspecified"))
    )
    (net (code "73") (name "unconnected-(U2-RST-Pad31)") (class "Default")
      (node (ref "U2") (pin "31") (pinfunction "RST_31") (pintype "unspecified"))
    )
    (net (code "74") (name "unconnected-(U6-Pad6)") (class "Default")
      (node (ref "U6") (pin "6") (pinfunction "6_6") (pintype "unspecified"))
    )
    (net (code "75") (name "unconnected-(U6-Pad11)") (class "Default")
      (node (ref "U6") (pin "11") (pinfunction "11_11") (pintype "unspecified"))
    )
    (net (code "76") (name "unconnected-(U10-Pad6)") (class "Default")
      (node (ref "U10") (pin "6") (pinfunction "6_6") (pintype "unspecified"))
    )
    (net (code "77") (name "unconnected-(U10-Pad6)_1") (class "Default")
      (node (ref "U10") (pin "6") (pinfunction "6_6") (pintype "unspecified"))
    )
    (net (code "78") (name "unconnected-(U10-Pad7)") (class "Default")
      (node (ref "U10") (pin "7") (pinfunction "7_7") (pintype "unspecified"))
    )
    (net (code "79") (name "unconnected-(U10-Pad8)") (class "Default")
      (node (ref "U10") (pin "8") (pinfunction "8_8") (pintype "unspecified"))
    )
    (net (code "80") (name "unconnected-(U10-Pad11)") (class "Default")
      (node (ref "U10") (pin "11") (pinfunction "11_11") (pintype "unspecified"))
    )
    (net (code "81") (name "unconnected-(U11-DB5-Pad10)") (class "Default")
      (node (ref "U11") (pin "10") (pinfunction "DB5_10") (pintype "unspecified"))
    )
    (net (code "82") (name "unconnected-(U11-DB6-Pad9)") (class "Default")
      (node (ref "U11") (pin "9") (pinfunction "DB6_9") (pintype "unspecified"))
    )
    (net (code "83") (name "unconnected-(U11-DB7-Pad8)") (class "Default")
      (node (ref "U11") (pin "8") (pinfunction "DB7_8") (pintype "unspecified"))
    )
    (net (code "84") (name "unconnected-(U11-DB8-Pad7)") (class "Default")
      (node (ref "U11") (pin "7") (pinfunction "DB8_7") (pintype "unspecified"))
    )
    (net (code "85") (name "unconnected-(U12-2-Padd)") (class "Default")
      (node (ref "U12") (pin "d") (pinfunction "2_d") (pintype "input"))
    )
    (net (code "86") (name "unconnected-(U12-3-Padc)") (class "Default")
      (node (ref "U12") (pin "c") (pinfunction "3_c") (pintype "input"))
    )
    (net (code "87") (name "unconnected-(U13-GND-Pad3)") (class "Default")
      (node (ref "U13") (pin "3") (pinfunction "GND_3") (pintype "unspecified"))
    )
    (net (code "88") (name "unconnected-(U13-VCC-Pad1)") (class "Default")
      (node (ref "U13") (pin "1") (pinfunction "VCC_1") (pintype "unspecified"))
    )
    (net (code "89") (name "unconnected-(U14-Pad1)") (class "Default")
      (node (ref "U14") (pin "1") (pinfunction "1_1") (pintype "unspecified"))
    )
    (net (code "90") (name "unconnected-(U18-Pad2)") (class "Default")
      (node (ref "U18") (pin "2") (pinfunction "2_2") (pintype "unspecified"))
    )
    (net (code "91") (name "unconnected-(U19-Pad2)") (class "Default")
      (node (ref "U19") (pin "2") (pinfunction "2_2") (pintype "unspecified"))
    )
    (net (code "92") (name "unconnected-(U20-Pad2)") (class "Default")
      (node (ref "U20") (pin "2") (pinfunction "2_2") (pintype "unspecified"))
    )
    (net (code "93") (name "unconnected-(U21-Pad2)") (class "Default")
      (node (ref "U21") (pin "2") (pinfunction "2_2") (pintype "unspecified"))
    )
    (net (code "94") (name "unconnected-(U22-Pad2)") (class "Default")
      (node (ref "U22") (pin "2") (pinfunction "2_2") (pintype "unspecified"))
    )
    (net (code "95") (name "unconnected-(U23-Pad2)") (class "Default")
      (node (ref "U23") (pin "2") (pinfunction "2_2") (pintype "unspecified"))
    )
    (net (code "96") (name "unconnected-(U24-1-Pada)") (class "Default")
      (node (ref "U24") (pin "a") (pinfunction "1_a") (pintype "input"))
    )
    (net (code "97") (name "unconnected-(U24-1-Padb)") (class "Default")
      (node (ref "U24") (pin "b") (pinfunction "1_b") (pintype "input"))
    )
    (net (code "98") (name "unconnected-(U24-2-Padd)") (class "Default")
      (node (ref "U24") (pin "d") (pinfunction "2_d") (pintype "input"))
    )
    (net (code "99") (name "unconnected-(U24-3-Padc)") (class "Default")
      (node (ref "U24") (pin "c") (pinfunction "3_c") (pintype "input"))
    )
    (net (code "100") (name "unconnected-(U25-1-Pada)") (class "Default")
      (node (ref "U25") (pin "a") (pinfunction "1_a") (pintype "input"))
    )
    (net (code "101") (name "unconnected-(U25-1-Padb)") (class "Default")
      (node (ref "U25") (pin "b") (pinfunction "1_b") (pintype "input"))
    )
    (net (code "102") (name "unconnected-(U25-2-Padd)") (class "Default")
      (node (ref "U25") (pin "d") (pinfunction "2_d") (pintype "input"))
    )
    (net (code "103") (name "unconnected-(U25-3-Padc)") (class "Default")
      (node (ref "U25") (pin "c") (pinfunction "3_c") (pintype "input"))
    )
  )
)
